# ATTAMI-Shield-bread.net
KiCad netlist of a schematic drawn in EAGLE
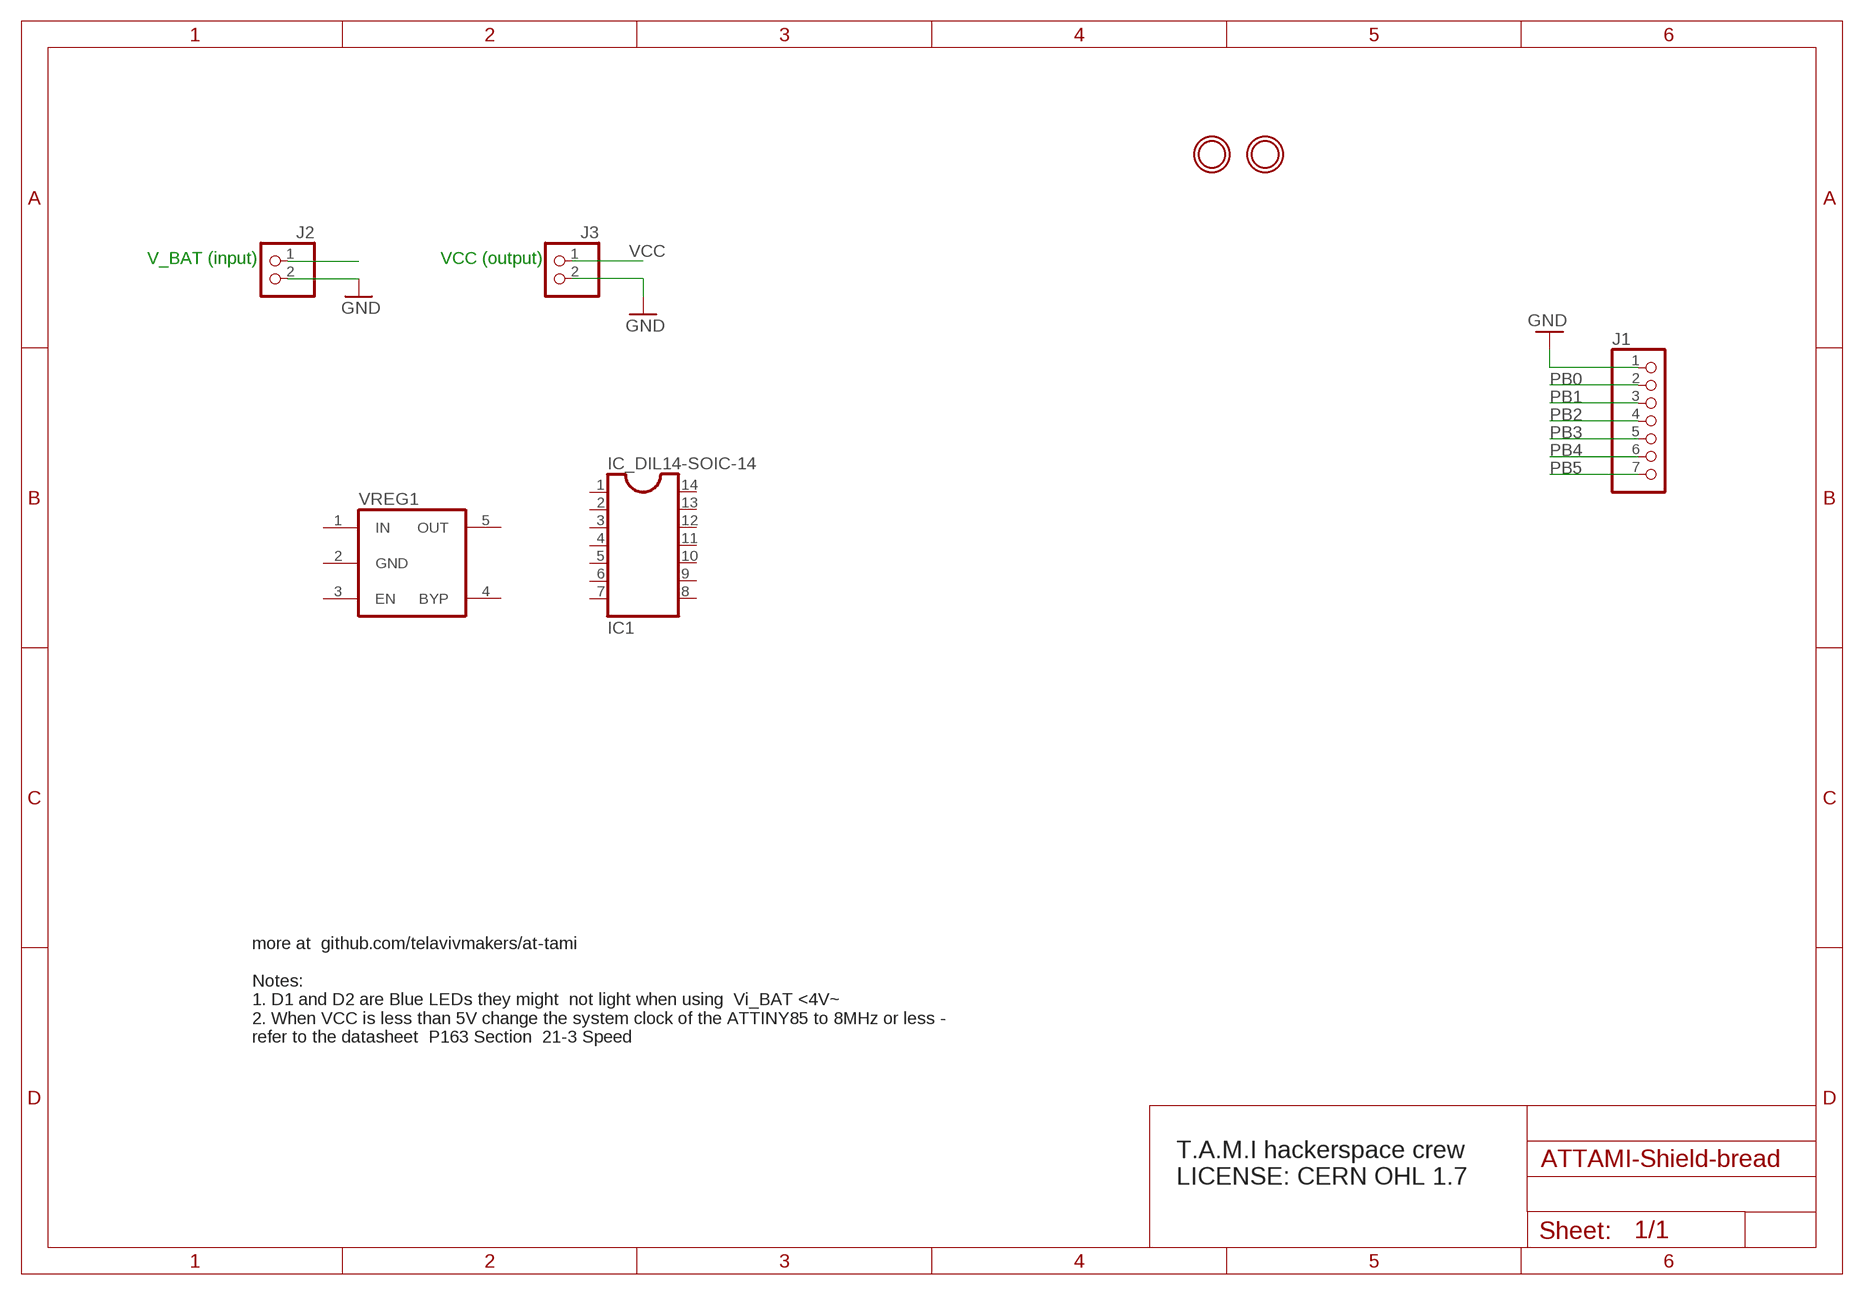
[diagram p0: schematic, sheet 1]

(export (version "E")
  (design (tool "Eeschema 10.0.6"))
  (components
    (comp (ref "IC1")
      (value "IC_DIL14-SOIC-14")
      (footprint "eagle-import:SOIC-14")
      (libsource (lib "eagle-import") (part "IC_DIL14-SOIC-14"))
    )
    (comp (ref "J1")
      (value "HEADER-1X7ROUND")
      (footprint "eagle-import:1X07_ROUND")
      (libsource (lib "eagle-import") (part "HEADER-1X7ROUND"))
    )
    (comp (ref "J2")
      (value "HEADER-1X2ROUND")
      (footprint "eagle-import:1X02_ROUND")
      (libsource (lib "eagle-import") (part "HEADER-1X2ROUND"))
    )
    (comp (ref "J3")
      (value "HEADER-1X2ROUND")
      (footprint "eagle-import:1X02_ROUND")
      (libsource (lib "eagle-import") (part "HEADER-1X2ROUND"))
    )
    (comp (ref "U$1")
      (value "MOUNTINGHOLE2.0")
      (footprint "eagle-import:MOUNTINGHOLE_2.0_PLATED")
      (libsource (lib "eagle-import") (part "MOUNTINGHOLE2.0"))
    )
    (comp (ref "U$2")
      (value "MOUNTINGHOLE2.0")
      (footprint "eagle-import:MOUNTINGHOLE_2.0_PLATED")
      (libsource (lib "eagle-import") (part "MOUNTINGHOLE2.0"))
    )
    (comp (ref "VREG1")
      (value "VREG_5PINS-SOT-23-5")
      (footprint "eagle-import:SOT-23-5")
      (libsource (lib "eagle-import") (part "VREG_5PINS-SOT-23-5"))
    )
  )
  (nets
    (net (code "1") (name "/PB0") (class "Default")
      (node (ref "J1") (pin "2") (pinfunction "2_2") (pintype "passive"))
    )
    (net (code "2") (name "/PB1") (class "Default")
      (node (ref "J1") (pin "3") (pinfunction "3_3") (pintype "passive"))
    )
    (net (code "3") (name "/PB2") (class "Default")
      (node (ref "J1") (pin "4") (pinfunction "4_4") (pintype "passive"))
    )
    (net (code "4") (name "/PB3") (class "Default")
      (node (ref "J1") (pin "5") (pinfunction "5_5") (pintype "passive"))
    )
    (net (code "5") (name "/PB4") (class "Default")
      (node (ref "J1") (pin "6") (pinfunction "6_6") (pintype "passive"))
    )
    (net (code "6") (name "/PB5") (class "Default")
      (node (ref "J1") (pin "7") (pinfunction "7_7") (pintype "passive"))
    )
    (net (code "7") (name "/VCC") (class "Default")
      (node (ref "J3") (pin "1") (pinfunction "1_1") (pintype "passive"))
    )
    (net (code "8") (name "GND") (class "Default")
      (node (ref "J1") (pin "1") (pinfunction "1_1") (pintype "passive"))
      (node (ref "J2") (pin "2") (pinfunction "2_2") (pintype "passive"))
      (node (ref "J3") (pin "2") (pinfunction "2_2") (pintype "passive"))
    )
    (net (code "9") (name "unconnected-(IC1-Pad1)") (class "Default")
      (node (ref "IC1") (pin "1") (pinfunction "1_1") (pintype "bidirectional"))
    )
    (net (code "10") (name "unconnected-(IC1-Pad2)") (class "Default")
      (node (ref "IC1") (pin "2") (pinfunction "2_2") (pintype "bidirectional"))
    )
    (net (code "11") (name "unconnected-(IC1-Pad3)") (class "Default")
      (node (ref "IC1") (pin "3") (pinfunction "3_3") (pintype "bidirectional"))
    )
    (net (code "12") (name "unconnected-(IC1-Pad4)") (class "Default")
      (node (ref "IC1") (pin "4") (pinfunction "4_4") (pintype "bidirectional"))
    )
    (net (code "13") (name "unconnected-(IC1-Pad5)") (class "Default")
      (node (ref "IC1") (pin "5") (pinfunction "5_5") (pintype "bidirectional"))
    )
    (net (code "14") (name "unconnected-(IC1-Pad6)") (class "Default")
      (node (ref "IC1") (pin "6") (pinfunction "6_6") (pintype "bidirectional"))
    )
    (net (code "15") (name "unconnected-(IC1-Pad7)") (class "Default")
      (node (ref "IC1") (pin "7") (pinfunction "7_7") (pintype "bidirectional"))
    )
    (net (code "16") (name "unconnected-(IC1-Pad8)") (class "Default")
      (node (ref "IC1") (pin "8") (pinfunction "8_8") (pintype "bidirectional"))
    )
    (net (code "17") (name "unconnected-(IC1-Pad9)") (class "Default")
      (node (ref "IC1") (pin "9") (pinfunction "9_9") (pintype "bidirectional"))
    )
    (net (code "18") (name "unconnected-(IC1-Pad10)") (class "Default")
      (node (ref "IC1") (pin "10") (pinfunction "10_10") (pintype "bidirectional"))
    )
    (net (code "19") (name "unconnected-(IC1-Pad11)") (class "Default")
      (node (ref "IC1") (pin "11") (pinfunction "11_11") (pintype "bidirectional"))
    )
    (net (code "20") (name "unconnected-(IC1-Pad12)") (class "Default")
      (node (ref "IC1") (pin "12") (pinfunction "12_12") (pintype "bidirectional"))
    )
    (net (code "21") (name "unconnected-(IC1-Pad13)") (class "Default")
      (node (ref "IC1") (pin "13") (pinfunction "13_13") (pintype "bidirectional"))
    )
    (net (code "22") (name "unconnected-(IC1-Pad14)") (class "Default")
      (node (ref "IC1") (pin "14") (pinfunction "14_14") (pintype "bidirectional"))
    )
    (net (code "23") (name "unconnected-(J2-Pad1)") (class "Default")
      (node (ref "J2") (pin "1") (pinfunction "1_1") (pintype "passive"))
    )
    (net (code "24") (name "unconnected-(VREG1-BYP-Pad4)") (class "Default")
      (node (ref "VREG1") (pin "4") (pinfunction "BYP_4") (pintype "bidirectional"))
    )
    (net (code "25") (name "unconnected-(VREG1-EN-Pad3)") (class "Default")
      (node (ref "VREG1") (pin "3") (pinfunction "EN_3") (pintype "bidirectional"))
    )
    (net (code "26") (name "unconnected-(VREG1-GND-Pad2)") (class "Default")
      (node (ref "VREG1") (pin "2") (pinfunction "GND_2") (pintype "bidirectional"))
    )
    (net (code "27") (name "unconnected-(VREG1-IN-Pad1)") (class "Default")
      (node (ref "VREG1") (pin "1") (pinfunction "IN_1") (pintype "bidirectional"))
    )
    (net (code "28") (name "unconnected-(VREG1-OUT-Pad5)") (class "Default")
      (node (ref "VREG1") (pin "5") (pinfunction "OUT_5") (pintype "bidirectional"))
    )
  )
)
